# NTcounterRX.net
KiCad netlist of a schematic drawn in EAGLE
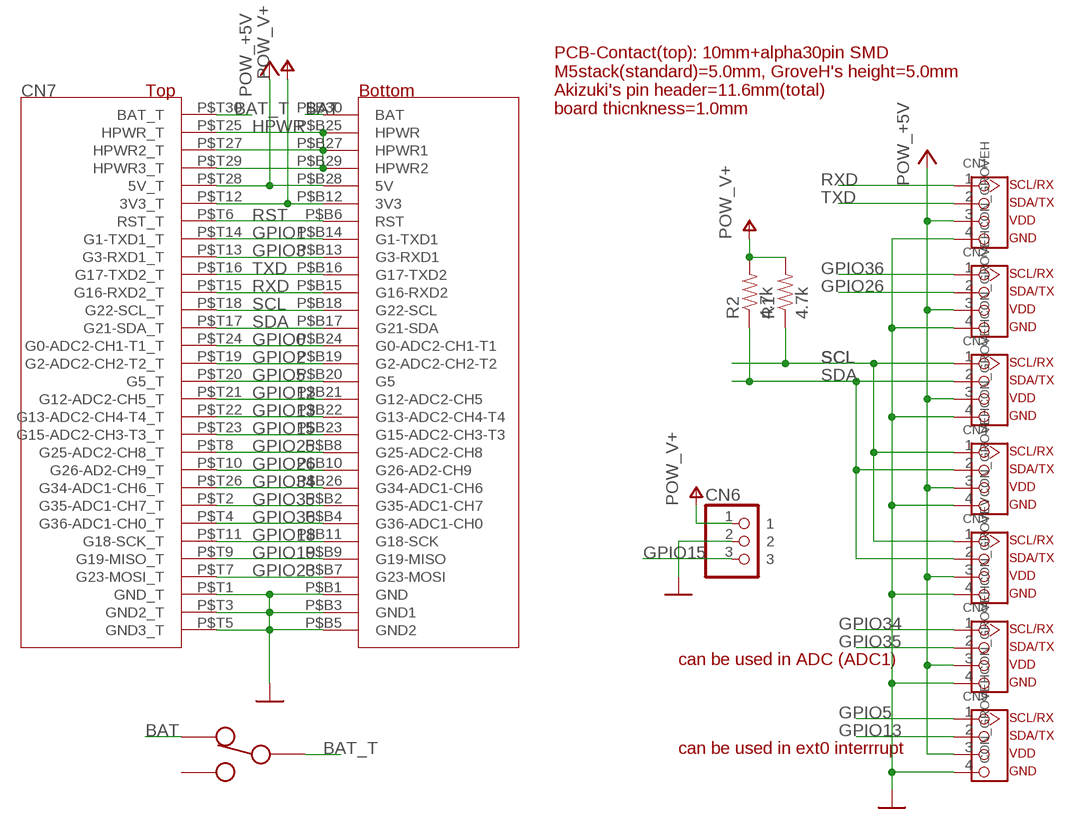
[diagram p0: schematic, sheet 1]

(export (version "E")
  (design (tool "Eeschema 10.0.6"))
  (components
    (comp (ref "CN1")
      (value "CON_GROVEH")
      (footprint "eagle-import:CON_GROVE_H")
      (libsource (lib "eagle-import") (part "CON_GROVEH"))
    )
    (comp (ref "CN2")
      (value "CON_GROVEH")
      (footprint "eagle-import:CON_GROVE_H")
      (libsource (lib "eagle-import") (part "CON_GROVEH"))
    )
    (comp (ref "CN3")
      (value "CON_GROVEH")
      (footprint "eagle-import:CON_GROVE_H")
      (libsource (lib "eagle-import") (part "CON_GROVEH"))
    )
    (comp (ref "CN4")
      (value "CON_GROVEH")
      (footprint "eagle-import:CON_GROVE_H")
      (libsource (lib "eagle-import") (part "CON_GROVEH"))
    )
    (comp (ref "CN5")
      (value "CON_GROVEV")
      (footprint "eagle-import:CON_GROVE_V")
      (libsource (lib "eagle-import") (part "CON_GROVEV"))
    )
    (comp (ref "CN6")
      (value "CON_PINHD-1X3R")
      (footprint "eagle-import:1X03R")
      (libsource (lib "eagle-import") (part "CON_PINHD-1X3R"))
    )
    (comp (ref "CN7")
      (value "MBUS_SEPBAT")
      (footprint "eagle-import:MBUS_SEP_BAT_SHORT")
      (libsource (lib "eagle-import") (part "MBUS_SEPBAT"))
    )
    (comp (ref "CN8")
      (value "CON_GROVEH")
      (footprint "eagle-import:CON_GROVE_H")
      (libsource (lib "eagle-import") (part "CON_GROVEH"))
    )
    (comp (ref "CN9")
      (value "CON_GROVEH")
      (footprint "eagle-import:CON_GROVE_H")
      (libsource (lib "eagle-import") (part "CON_GROVEH"))
    )
    (comp (ref "R1")
      (value "4.7k")
      (footprint "eagle-import:0603")
      (libsource (lib "eagle-import") (part "RES0603"))
    )
    (comp (ref "R2")
      (value "4.7k")
      (footprint "eagle-import:0603")
      (libsource (lib "eagle-import") (part "RES0603"))
    )
    (comp (ref "SW1")
      (value "SW_SLIDESK12D01")
      (footprint "eagle-import:SW_SK12D01")
      (libsource (lib "eagle-import") (part "SW_SLIDESK12D01"))
    )
  )
  (nets
    (net (code "1") (name "/BAT") (class "Default")
      (node (ref "CN7") (pin "P$B30") (pinfunction "BAT_P$B30") (pintype "bidirectional"))
      (node (ref "SW1") (pin "P$1") (pinfunction "P$1_P$1") (pintype "power_in"))
    )
    (net (code "2") (name "/BAT_T") (class "Default")
      (node (ref "CN7") (pin "P$T30") (pinfunction "BAT_T_P$T30") (pintype "bidirectional"))
      (node (ref "SW1") (pin "P$2") (pinfunction "P$2_P$2") (pintype "power_in"))
    )
    (net (code "3") (name "/GPIO0") (class "Default")
      (node (ref "CN7") (pin "P$B24") (pinfunction "G0-ADC2-CH1-T1_P$B24") (pintype "bidirectional"))
      (node (ref "CN7") (pin "P$T24") (pinfunction "G0-ADC2-CH1-T1_T_P$T24") (pintype "bidirectional"))
    )
    (net (code "4") (name "/GPIO1") (class "Default")
      (node (ref "CN7") (pin "P$B14") (pinfunction "G1-TXD1_P$B14") (pintype "bidirectional"))
      (node (ref "CN7") (pin "P$T14") (pinfunction "G1-TXD1_T_P$T14") (pintype "bidirectional"))
    )
    (net (code "5") (name "/GPIO2") (class "Default")
      (node (ref "CN7") (pin "P$B19") (pinfunction "G2-ADC2-CH2-T2_P$B19") (pintype "bidirectional"))
      (node (ref "CN7") (pin "P$T19") (pinfunction "G2-ADC2-CH2-T2_T_P$T19") (pintype "bidirectional"))
    )
    (net (code "6") (name "/GPIO3") (class "Default")
      (node (ref "CN7") (pin "P$B13") (pinfunction "G3-RXD1_P$B13") (pintype "bidirectional"))
      (node (ref "CN7") (pin "P$T13") (pinfunction "G3-RXD1_T_P$T13") (pintype "bidirectional"))
    )
    (net (code "7") (name "/GPIO5") (class "Default")
      (node (ref "CN7") (pin "P$B20") (pinfunction "G5_P$B20") (pintype "bidirectional"))
      (node (ref "CN7") (pin "P$T20") (pinfunction "G5_T_P$T20") (pintype "bidirectional"))
      (node (ref "CN9") (pin "1") (pinfunction "1_1") (pintype "bidirectional"))
    )
    (net (code "8") (name "/GPIO12") (class "Default")
      (node (ref "CN7") (pin "P$B21") (pinfunction "G12-ADC2-CH5_P$B21") (pintype "bidirectional"))
      (node (ref "CN7") (pin "P$T21") (pinfunction "G12-ADC2-CH5_T_P$T21") (pintype "bidirectional"))
    )
    (net (code "9") (name "/GPIO13") (class "Default")
      (node (ref "CN7") (pin "P$B22") (pinfunction "G13-ADC2-CH4-T4_P$B22") (pintype "bidirectional"))
      (node (ref "CN7") (pin "P$T22") (pinfunction "G13-ADC2-CH4-T4_T_P$T22") (pintype "bidirectional"))
      (node (ref "CN9") (pin "2") (pinfunction "2_2") (pintype "bidirectional"))
    )
    (net (code "10") (name "/GPIO15") (class "Default")
      (node (ref "CN6") (pin "3") (pinfunction "3_3") (pintype "passive"))
      (node (ref "CN7") (pin "P$B23") (pinfunction "G15-ADC2-CH3-T3_P$B23") (pintype "bidirectional"))
      (node (ref "CN7") (pin "P$T23") (pinfunction "G15-ADC2-CH3-T3_T_P$T23") (pintype "bidirectional"))
    )
    (net (code "11") (name "/GPIO18") (class "Default")
      (node (ref "CN7") (pin "P$B11") (pinfunction "G18-SCK_P$B11") (pintype "bidirectional"))
      (node (ref "CN7") (pin "P$T11") (pinfunction "G18-SCK_T_P$T11") (pintype "bidirectional"))
    )
    (net (code "12") (name "/GPIO19") (class "Default")
      (node (ref "CN7") (pin "P$B9") (pinfunction "G19-MISO_P$B9") (pintype "bidirectional"))
      (node (ref "CN7") (pin "P$T9") (pinfunction "G19-MISO_T_P$T9") (pintype "bidirectional"))
    )
    (net (code "13") (name "/GPIO23") (class "Default")
      (node (ref "CN7") (pin "P$B7") (pinfunction "G23-MOSI_P$B7") (pintype "bidirectional"))
      (node (ref "CN7") (pin "P$T7") (pinfunction "G23-MOSI_T_P$T7") (pintype "bidirectional"))
    )
    (net (code "14") (name "/GPIO25") (class "Default")
      (node (ref "CN7") (pin "P$B8") (pinfunction "G25-ADC2-CH8_P$B8") (pintype "bidirectional"))
      (node (ref "CN7") (pin "P$T8") (pinfunction "G25-ADC2-CH8_T_P$T8") (pintype "bidirectional"))
    )
    (net (code "15") (name "/GPIO26") (class "Default")
      (node (ref "CN2") (pin "2") (pinfunction "2_2") (pintype "bidirectional"))
      (node (ref "CN7") (pin "P$B10") (pinfunction "G26-AD2-CH9_P$B10") (pintype "bidirectional"))
      (node (ref "CN7") (pin "P$T10") (pinfunction "G26-AD2-CH9_T_P$T10") (pintype "bidirectional"))
    )
    (net (code "16") (name "/GPIO34") (class "Default")
      (node (ref "CN7") (pin "P$B26") (pinfunction "G34-ADC1-CH6_P$B26") (pintype "bidirectional"))
      (node (ref "CN7") (pin "P$T26") (pinfunction "G34-ADC1-CH6_T_P$T26") (pintype "bidirectional"))
      (node (ref "CN8") (pin "1") (pinfunction "1_1") (pintype "bidirectional"))
    )
    (net (code "17") (name "/GPIO35") (class "Default")
      (node (ref "CN7") (pin "P$B2") (pinfunction "G35-ADC1-CH7_P$B2") (pintype "bidirectional"))
      (node (ref "CN7") (pin "P$T2") (pinfunction "G35-ADC1-CH7_T_P$T2") (pintype "bidirectional"))
      (node (ref "CN8") (pin "2") (pinfunction "2_2") (pintype "bidirectional"))
    )
    (net (code "18") (name "/GPIO36") (class "Default")
      (node (ref "CN2") (pin "1") (pinfunction "1_1") (pintype "bidirectional"))
      (node (ref "CN7") (pin "P$B4") (pinfunction "G36-ADC1-CH0_P$B4") (pintype "bidirectional"))
      (node (ref "CN7") (pin "P$T4") (pinfunction "G36-ADC1-CH0_T_P$T4") (pintype "bidirectional"))
    )
    (net (code "19") (name "/HPWR") (class "Default")
      (node (ref "CN7") (pin "P$B25") (pinfunction "HPWR_P$B25") (pintype "bidirectional"))
      (node (ref "CN7") (pin "P$B27") (pinfunction "HPWR1_P$B27") (pintype "bidirectional"))
      (node (ref "CN7") (pin "P$B29") (pinfunction "HPWR2_P$B29") (pintype "bidirectional"))
      (node (ref "CN7") (pin "P$T25") (pinfunction "HPWR_T_P$T25") (pintype "bidirectional"))
      (node (ref "CN7") (pin "P$T27") (pinfunction "HPWR2_T_P$T27") (pintype "bidirectional"))
      (node (ref "CN7") (pin "P$T29") (pinfunction "HPWR3_T_P$T29") (pintype "bidirectional"))
    )
    (net (code "20") (name "/P$3") (class "Default")
      (node (ref "SW1") (pin "P$3") (pinfunction "P$3_P$3") (pintype "power_in"))
    )
    (net (code "21") (name "/RST") (class "Default")
      (node (ref "CN7") (pin "P$B6") (pinfunction "RST_P$B6") (pintype "bidirectional"))
      (node (ref "CN7") (pin "P$T6") (pinfunction "RST_T_P$T6") (pintype "bidirectional"))
    )
    (net (code "22") (name "/RXD") (class "Default")
      (node (ref "CN1") (pin "1") (pinfunction "1_1") (pintype "bidirectional"))
      (node (ref "CN7") (pin "P$B15") (pinfunction "G16-RXD2_P$B15") (pintype "bidirectional"))
      (node (ref "CN7") (pin "P$T15") (pinfunction "G16-RXD2_T_P$T15") (pintype "bidirectional"))
    )
    (net (code "23") (name "/SCL") (class "Default")
      (node (ref "CN3") (pin "1") (pinfunction "1_1") (pintype "bidirectional"))
      (node (ref "CN4") (pin "1") (pinfunction "1_1") (pintype "bidirectional"))
      (node (ref "CN5") (pin "1") (pinfunction "1_1") (pintype "bidirectional"))
      (node (ref "CN7") (pin "P$B18") (pinfunction "G22-SCL_P$B18") (pintype "bidirectional"))
      (node (ref "CN7") (pin "P$T18") (pinfunction "G22-SCL_T_P$T18") (pintype "bidirectional"))
      (node (ref "R1") (pin "1") (pinfunction "1_1") (pintype "passive"))
    )
    (net (code "24") (name "/SDA") (class "Default")
      (node (ref "CN3") (pin "2") (pinfunction "2_2") (pintype "bidirectional"))
      (node (ref "CN4") (pin "2") (pinfunction "2_2") (pintype "bidirectional"))
      (node (ref "CN5") (pin "2") (pinfunction "2_2") (pintype "bidirectional"))
      (node (ref "CN7") (pin "P$B17") (pinfunction "G21-SDA_P$B17") (pintype "bidirectional"))
      (node (ref "CN7") (pin "P$T17") (pinfunction "G21-SDA_T_P$T17") (pintype "bidirectional"))
      (node (ref "R2") (pin "1") (pinfunction "1_1") (pintype "passive"))
    )
    (net (code "25") (name "/TXD") (class "Default")
      (node (ref "CN1") (pin "2") (pinfunction "2_2") (pintype "bidirectional"))
      (node (ref "CN7") (pin "P$B16") (pinfunction "G17-TXD2_P$B16") (pintype "bidirectional"))
      (node (ref "CN7") (pin "P$T16") (pinfunction "G17-TXD2_T_P$T16") (pintype "bidirectional"))
    )
    (net (code "26") (name "POW_+5V") (class "Default")
      (node (ref "CN1") (pin "3") (pinfunction "3_3") (pintype "bidirectional"))
      (node (ref "CN2") (pin "3") (pinfunction "3_3") (pintype "bidirectional"))
      (node (ref "CN3") (pin "3") (pinfunction "3_3") (pintype "bidirectional"))
      (node (ref "CN4") (pin "3") (pinfunction "3_3") (pintype "bidirectional"))
      (node (ref "CN5") (pin "3") (pinfunction "3_3") (pintype "bidirectional"))
      (node (ref "CN7") (pin "P$B28") (pinfunction "5V_P$B28") (pintype "bidirectional"))
      (node (ref "CN7") (pin "P$T28") (pinfunction "5V_T_P$T28") (pintype "bidirectional"))
      (node (ref "CN8") (pin "3") (pinfunction "3_3") (pintype "bidirectional"))
      (node (ref "CN9") (pin "3") (pinfunction "3_3") (pintype "bidirectional"))
    )
    (net (code "27") (name "POW_GND") (class "Default")
      (node (ref "CN1") (pin "4") (pinfunction "4_4") (pintype "bidirectional"))
      (node (ref "CN2") (pin "4") (pinfunction "4_4") (pintype "bidirectional"))
      (node (ref "CN3") (pin "4") (pinfunction "4_4") (pintype "bidirectional"))
      (node (ref "CN4") (pin "4") (pinfunction "4_4") (pintype "bidirectional"))
      (node (ref "CN5") (pin "4") (pinfunction "4_4") (pintype "bidirectional"))
      (node (ref "CN6") (pin "2") (pinfunction "2_2") (pintype "passive"))
      (node (ref "CN7") (pin "P$B1") (pinfunction "GND_P$B1") (pintype "bidirectional"))
      (node (ref "CN7") (pin "P$B3") (pinfunction "GND1_P$B3") (pintype "bidirectional"))
      (node (ref "CN7") (pin "P$B5") (pinfunction "GND2_P$B5") (pintype "bidirectional"))
      (node (ref "CN7") (pin "P$T1") (pinfunction "GND_T_P$T1") (pintype "bidirectional"))
      (node (ref "CN7") (pin "P$T3") (pinfunction "GND2_T_P$T3") (pintype "bidirectional"))
      (node (ref "CN7") (pin "P$T5") (pinfunction "GND3_T_P$T5") (pintype "bidirectional"))
      (node (ref "CN8") (pin "4") (pinfunction "4_4") (pintype "bidirectional"))
      (node (ref "CN9") (pin "4") (pinfunction "4_4") (pintype "bidirectional"))
    )
    (net (code "28") (name "POW_V+") (class "Default")
      (node (ref "CN6") (pin "1") (pinfunction "1_1") (pintype "passive"))
      (node (ref "CN7") (pin "P$B12") (pinfunction "3V3_P$B12") (pintype "bidirectional"))
      (node (ref "CN7") (pin "P$T12") (pinfunction "3V3_T_P$T12") (pintype "bidirectional"))
      (node (ref "R1") (pin "2") (pinfunction "2_2") (pintype "passive"))
      (node (ref "R2") (pin "2") (pinfunction "2_2") (pintype "passive"))
    )
  )
)
